# ScubaSteve_PWR.net
KiCad netlist of a schematic drawn in EAGLE
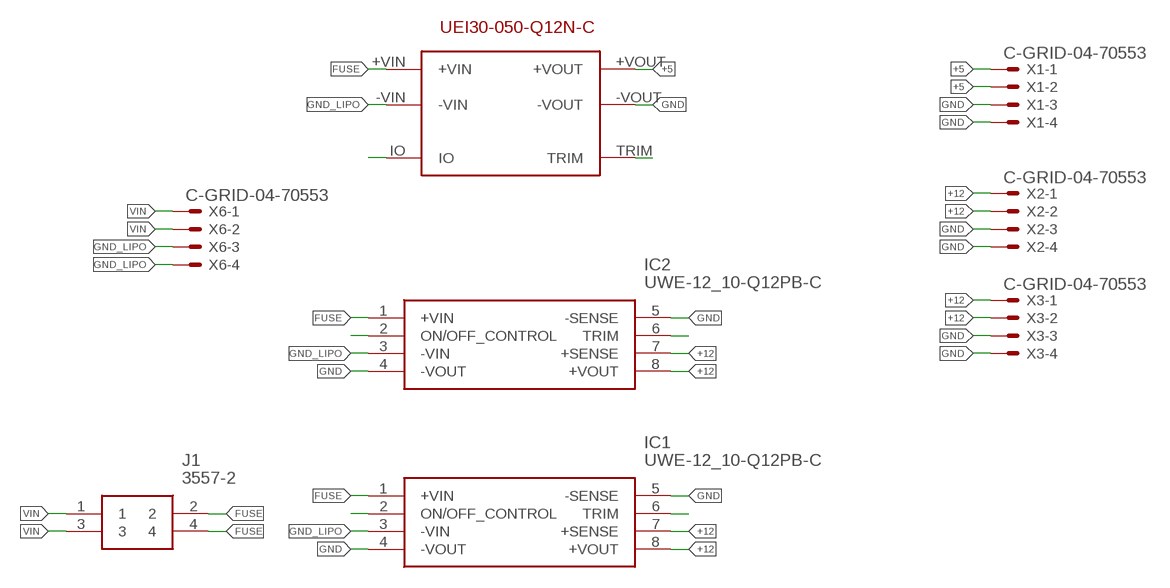
[diagram p0: schematic, sheet 1]

(export (version "E")
  (design (tool "Eeschema 10.0.6"))
  (components
    (comp (ref "IC1")
      (value "UWE-12_10-Q12PB-C")
      (footprint "eagle-import:UWE520Q48NC")
      (fields
        (field (name "MANUFACTURER_PART_NUMBER") "UWE-12/10-Q12PB-C")
        (field (name "MOUSER_PART_NUMBER") "580-UWE-12/10Q12PBC")
      )
      (libsource (lib "eagle-import") (part "UWE-12_10-Q12PB-C"))
    )
    (comp (ref "IC2")
      (value "UWE-12_10-Q12PB-C")
      (footprint "eagle-import:UWE520Q48NC")
      (fields
        (field (name "MANUFACTURER_PART_NUMBER") "UWE-12/10-Q12PB-C")
        (field (name "MOUSER_PART_NUMBER") "580-UWE-12/10Q12PBC")
      )
      (libsource (lib "eagle-import") (part "UWE-12_10-Q12PB-C"))
    )
    (comp (ref "J1")
      (value "3557-2")
      (footprint "eagle-import:3557-2")
      (fields (field (name "MOUSER_PART_NUMBER") "534-3557-2"))
      (libsource (lib "eagle-import") (part "3557-2"))
    )
    (comp (ref "U$1")
      (value "UEI30-050-Q12N-C")
      (footprint "eagle-import:UEI30-050-Q12N-C")
      (libsource (lib "eagle-import") (part "UEI30-050-Q12N-C"))
    )
    (comp (ref "X1")
      (value "C-GRID-04-70553")
      (footprint "eagle-import:70553-04")
      (fields (field (name "MF") "MOLEX"))
      (libsource (lib "eagle-import") (part "C-GRID-04-70553"))
    )
    (comp (ref "X2")
      (value "C-GRID-04-70553")
      (footprint "eagle-import:70553-04")
      (fields (field (name "MF") "MOLEX"))
      (libsource (lib "eagle-import") (part "C-GRID-04-70553"))
    )
    (comp (ref "X3")
      (value "C-GRID-04-70553")
      (footprint "eagle-import:70553-04")
      (fields (field (name "MF") "MOLEX"))
      (libsource (lib "eagle-import") (part "C-GRID-04-70553"))
    )
    (comp (ref "X6")
      (value "C-GRID-04-70553")
      (footprint "eagle-import:70553-04")
      (fields (field (name "MF") "MOLEX"))
      (libsource (lib "eagle-import") (part "C-GRID-04-70553"))
    )
  )
  (nets
    (net (code "1") (name "+5") (class "Default")
      (node (ref "U$1") (pin "+VOUT") (pinfunction "+VOUT_+VOUT") (pintype "bidirectional"))
      (node (ref "X1") (pin "1") (pinfunction "S_1") (pintype "passive"))
      (node (ref "X1") (pin "2") (pinfunction "S_2") (pintype "passive"))
    )
    (net (code "2") (name "+12") (class "Default")
      (node (ref "IC1") (pin "7") (pinfunction "+SENSE_7") (pintype "bidirectional"))
      (node (ref "IC1") (pin "8") (pinfunction "+VOUT_8") (pintype "output"))
      (node (ref "IC2") (pin "7") (pinfunction "+SENSE_7") (pintype "bidirectional"))
      (node (ref "IC2") (pin "8") (pinfunction "+VOUT_8") (pintype "output"))
      (node (ref "X2") (pin "1") (pinfunction "S_1") (pintype "passive"))
      (node (ref "X2") (pin "2") (pinfunction "S_2") (pintype "passive"))
      (node (ref "X3") (pin "1") (pinfunction "S_1") (pintype "passive"))
      (node (ref "X3") (pin "2") (pinfunction "S_2") (pintype "passive"))
    )
    (net (code "3") (name "FUSE") (class "Default")
      (node (ref "IC1") (pin "1") (pinfunction "+VIN_1") (pintype "input"))
      (node (ref "IC2") (pin "1") (pinfunction "+VIN_1") (pintype "input"))
      (node (ref "J1") (pin "2") (pinfunction "2_2") (pintype "bidirectional"))
      (node (ref "J1") (pin "4") (pinfunction "4_4") (pintype "bidirectional"))
      (node (ref "U$1") (pin "+VIN") (pinfunction "+VIN_+VIN") (pintype "bidirectional"))
    )
    (net (code "4") (name "GND") (class "Default")
      (node (ref "IC1") (pin "4") (pinfunction "-VOUT_4") (pintype "output"))
      (node (ref "IC1") (pin "5") (pinfunction "-SENSE_5") (pintype "bidirectional"))
      (node (ref "IC2") (pin "4") (pinfunction "-VOUT_4") (pintype "output"))
      (node (ref "IC2") (pin "5") (pinfunction "-SENSE_5") (pintype "bidirectional"))
      (node (ref "U$1") (pin "-VOUT") (pinfunction "-VOUT_-VOUT") (pintype "bidirectional"))
      (node (ref "X1") (pin "3") (pinfunction "S_3") (pintype "passive"))
      (node (ref "X1") (pin "4") (pinfunction "S_4") (pintype "passive"))
      (node (ref "X2") (pin "3") (pinfunction "S_3") (pintype "passive"))
      (node (ref "X2") (pin "4") (pinfunction "S_4") (pintype "passive"))
      (node (ref "X3") (pin "3") (pinfunction "S_3") (pintype "passive"))
      (node (ref "X3") (pin "4") (pinfunction "S_4") (pintype "passive"))
    )
    (net (code "5") (name "GND_LIPO") (class "Default")
      (node (ref "IC1") (pin "3") (pinfunction "-VIN_3") (pintype "input"))
      (node (ref "IC2") (pin "3") (pinfunction "-VIN_3") (pintype "input"))
      (node (ref "U$1") (pin "-VIN") (pinfunction "-VIN_-VIN") (pintype "bidirectional"))
      (node (ref "X6") (pin "3") (pinfunction "S_3") (pintype "passive"))
      (node (ref "X6") (pin "4") (pinfunction "S_4") (pintype "passive"))
    )
    (net (code "6") (name "VIN") (class "Default")
      (node (ref "J1") (pin "1") (pinfunction "1_1") (pintype "bidirectional"))
      (node (ref "J1") (pin "3") (pinfunction "3_3") (pintype "bidirectional"))
      (node (ref "X6") (pin "1") (pinfunction "S_1") (pintype "passive"))
      (node (ref "X6") (pin "2") (pinfunction "S_2") (pintype "passive"))
    )
    (net (code "7") (name "unconnected-(IC1-ON{slash}OFF_CONTROL-Pad2)") (class "Default")
      (node (ref "IC1") (pin "2") (pinfunction "ON/OFF_CONTROL_2") (pintype "bidirectional"))
    )
    (net (code "8") (name "unconnected-(IC1-TRIM-Pad6)") (class "Default")
      (node (ref "IC1") (pin "6") (pinfunction "TRIM_6") (pintype "bidirectional"))
    )
    (net (code "9") (name "unconnected-(IC2-ON{slash}OFF_CONTROL-Pad2)") (class "Default")
      (node (ref "IC2") (pin "2") (pinfunction "ON/OFF_CONTROL_2") (pintype "bidirectional"))
    )
    (net (code "10") (name "unconnected-(IC2-TRIM-Pad6)") (class "Default")
      (node (ref "IC2") (pin "6") (pinfunction "TRIM_6") (pintype "bidirectional"))
    )
    (net (code "11") (name "unconnected-(U$1-PadIO)") (class "Default")
      (node (ref "U$1") (pin "IO") (pinfunction "IO_IO") (pintype "bidirectional"))
    )
    (net (code "12") (name "unconnected-(U$1-PadTRIM)") (class "Default")
      (node (ref "U$1") (pin "TRIM") (pinfunction "TRIM_TRIM") (pintype "bidirectional"))
    )
  )
)
